# Launchpad_2021-03-10.net
KiCad netlist of a schematic drawn in EasyEDA
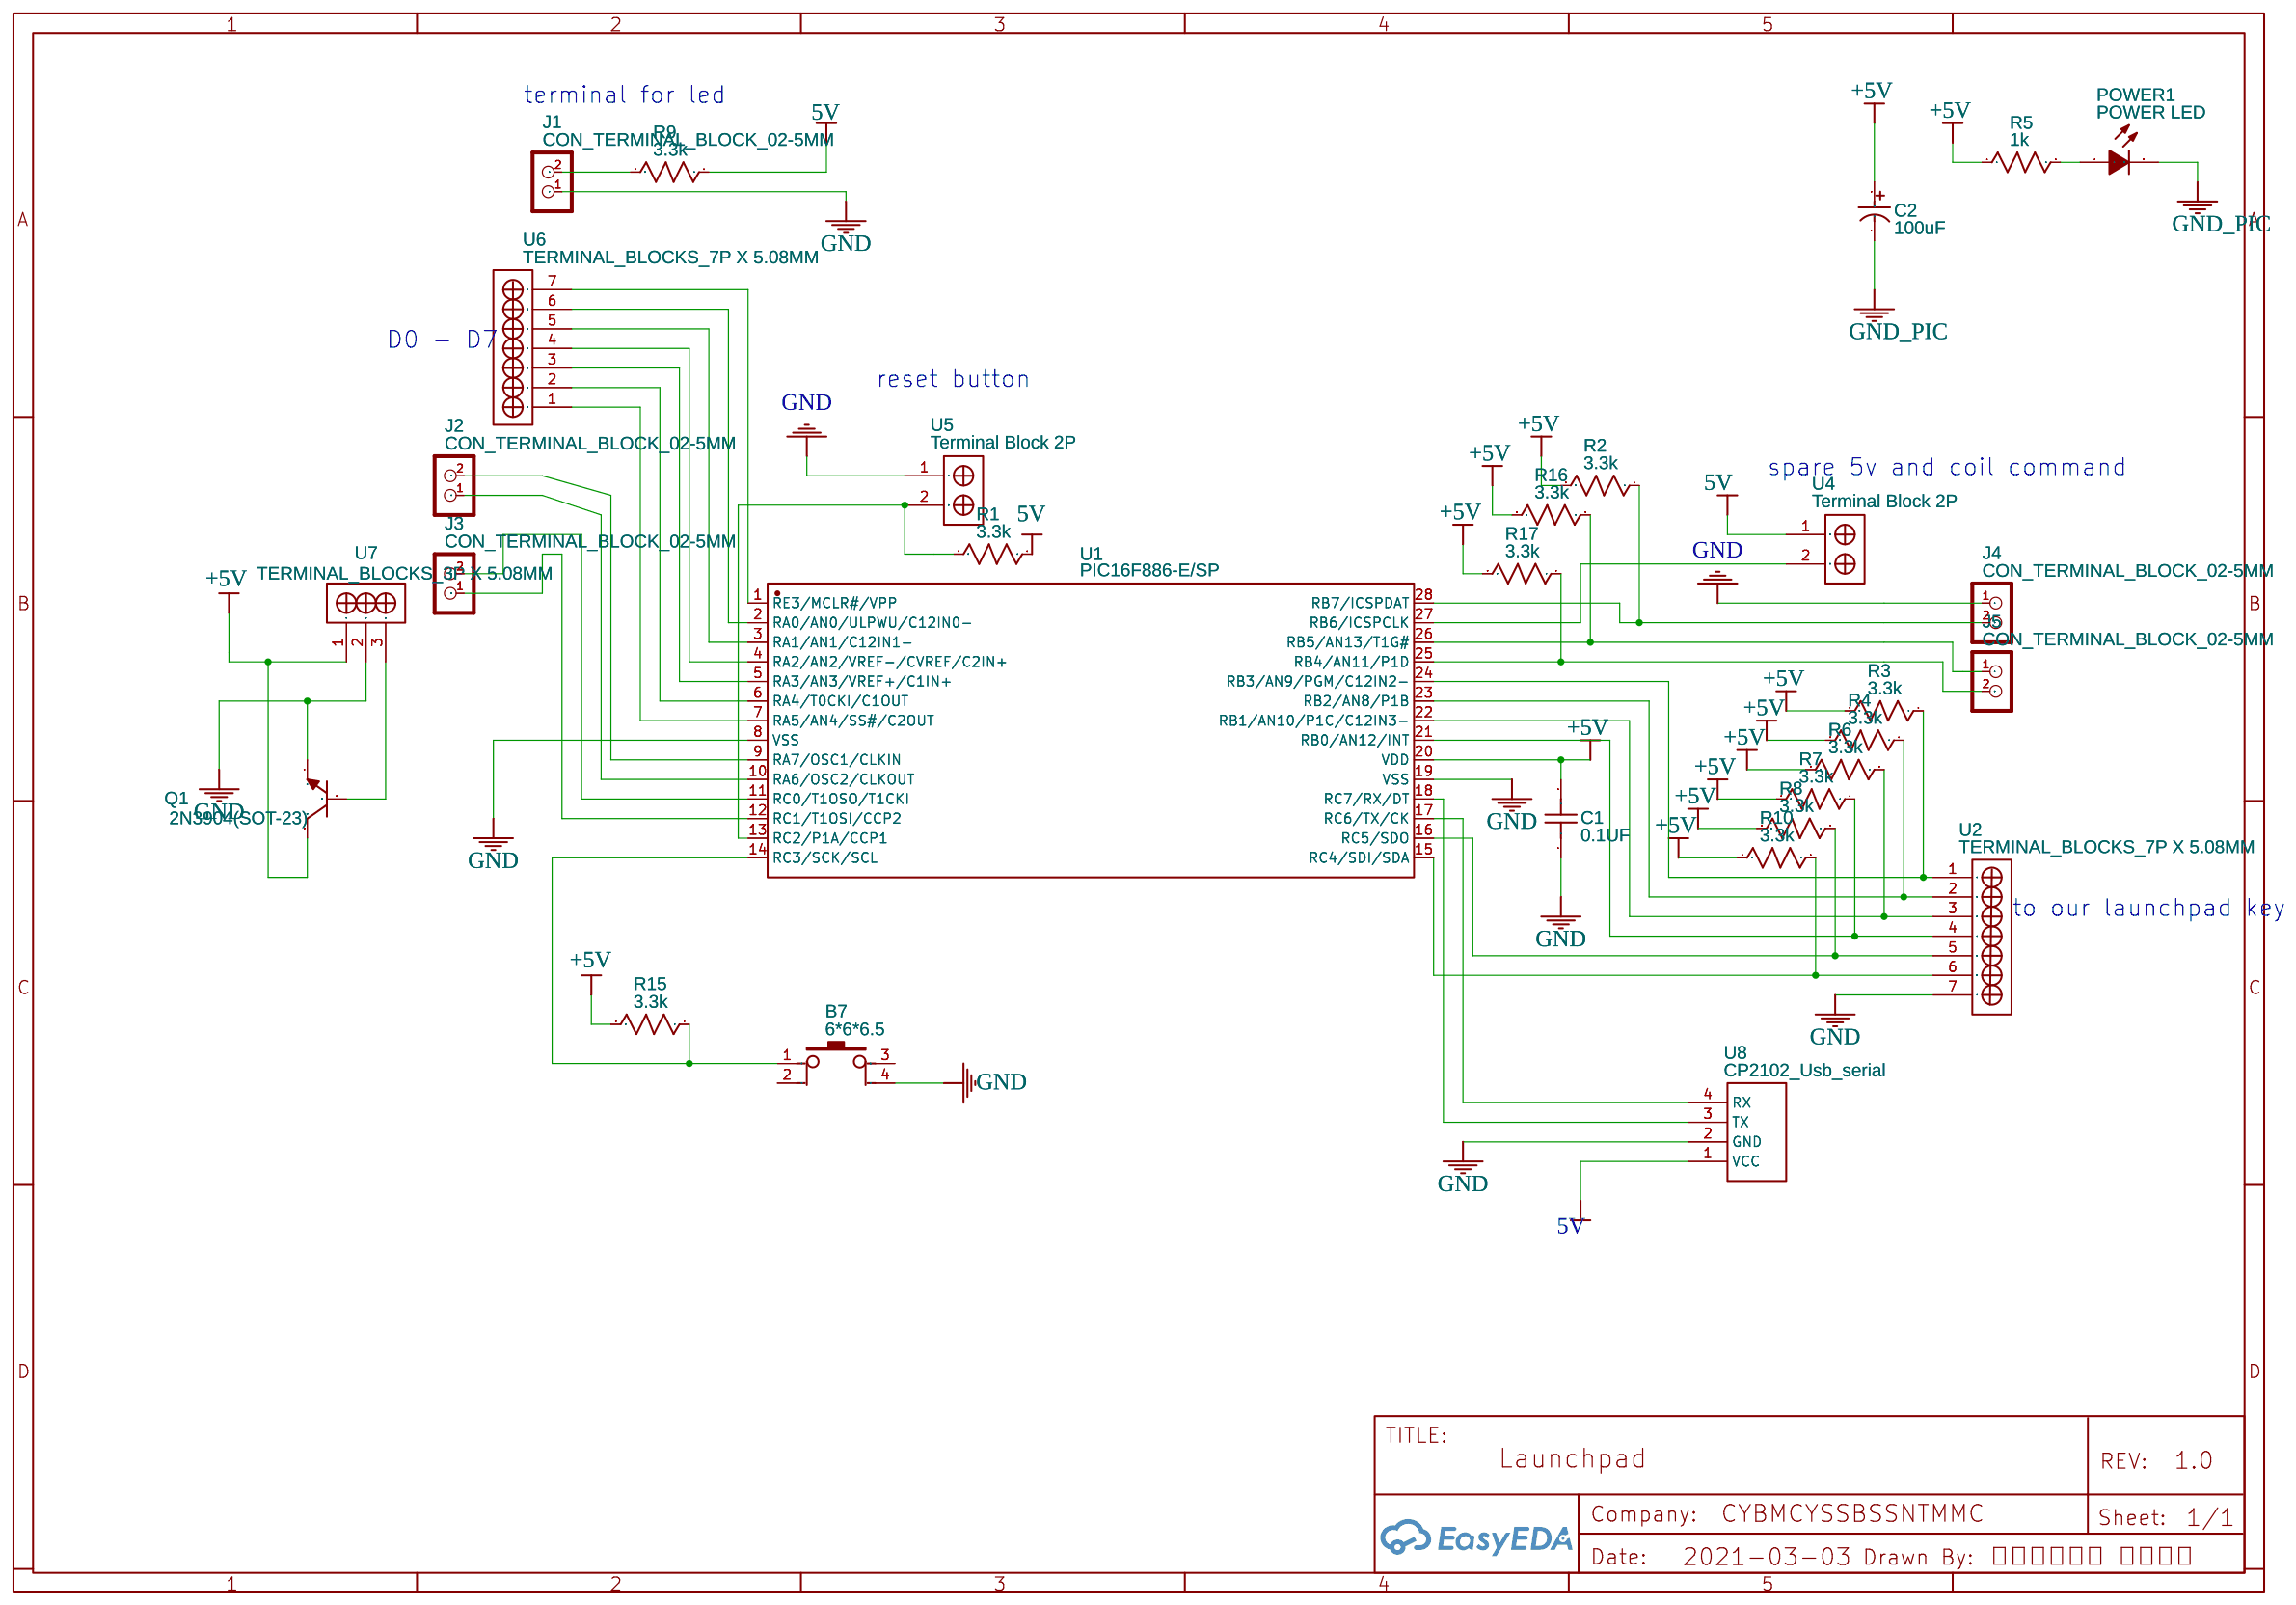
[diagram p0: schematic sheet]

(export (version "E")
  (design (tool "Eeschema 10.0.6"))
  (components
    (comp (ref "B7")
      (value "6*6*6.5")
      (fields
        (field (name "BOM_Manufacturer Part") "6*6*6.5Plastic head,260G, 0.25mm,Straight line")
        (field (name "BOM_Supplier Part") "C71841")
      )
      (libsource (lib "") (part "Unknown_420_-270"))
    )
    (comp (ref "C1")
      (value "0.1UF")
      (fields
        (field (name "BOM_Manufacturer Part") "250V 0.1UF 5% CBBCapacitor")
        (field (name "BOM_Supplier Part") "C46804")
      )
      (libsource (lib "") (part "250V 0.1UF 5% CBBCapacitor"))
    )
    (comp (ref "C2")
      (value "100uF")
      (fields (field (name "BOM_Manufacturer Part") "100uf/10V") (field (name "BOM_Supplier Part") "C2035"))
      (libsource (lib "") (part "100uf/10V"))
    )
    (comp (ref "J1")
      (value "CON_TERMINAL_BLOCK_02-5MM")
      (libsource (lib "") (part "CON_TERMINAL_BLOCK_02-5MM"))
    )
    (comp (ref "J2")
      (value "CON_TERMINAL_BLOCK_02-5MM")
      (libsource (lib "") (part "CON_TERMINAL_BLOCK_02-5MM"))
    )
    (comp (ref "J3")
      (value "CON_TERMINAL_BLOCK_02-5MM")
      (libsource (lib "") (part "CON_TERMINAL_BLOCK_02-5MM"))
    )
    (comp (ref "J4")
      (value "CON_TERMINAL_BLOCK_02-5MM")
      (libsource (lib "") (part "CON_TERMINAL_BLOCK_02-5MM_1"))
    )
    (comp (ref "J5")
      (value "CON_TERMINAL_BLOCK_02-5MM")
      (libsource (lib "") (part "CON_TERMINAL_BLOCK_02-5MM_1"))
    )
    (comp (ref "POWER1")
      (value "POWER LED")
      (fields (field (name "BOM_Manufacturer Part") "φ3 Red") (field (name "BOM_Supplier Part") "C39928"))
      (libsource (lib "") (part "Unknown_1075_-735"))
    )
    (comp (ref "Q1")
      (value "2N3904(SOT-23)")
      (fields
        (field (name "BOM_Manufacturer Part") "2n3904S-RTK/PS")
        (field (name "BOM_Supplier Part") "C18536")
      )
      (libsource (lib "") (part "2N3904(SOT-23)"))
    )
    (comp (ref "R1")
      (value "3.3k")
      (fields (field (name "BOM_Manufacturer Part") "?"))
      (libsource (lib "") (part "Res_AXIAL-0.3(1/8W)_US"))
    )
    (comp (ref "R2")
      (value "3.3k")
      (fields (field (name "BOM_Manufacturer Part") "?"))
      (libsource (lib "") (part "Res_AXIAL-0.3(1/8W)_US"))
    )
    (comp (ref "R3")
      (value "3.3k")
      (fields (field (name "BOM_Manufacturer Part") "?"))
      (libsource (lib "") (part "Res_AXIAL-0.3(1/8W)_US"))
    )
    (comp (ref "R4")
      (value "3.3k")
      (fields (field (name "BOM_Manufacturer Part") "?"))
      (libsource (lib "") (part "Res_AXIAL-0.3(1/8W)_US"))
    )
    (comp (ref "R5")
      (value "1k")
      (fields (field (name "BOM_Manufacturer Part") "?"))
      (libsource (lib "") (part "Res_AXIAL-0.3(1/8W)_US_1"))
    )
    (comp (ref "R6")
      (value "3.3k")
      (fields (field (name "BOM_Manufacturer Part") "?"))
      (libsource (lib "") (part "Res_AXIAL-0.3(1/8W)_US"))
    )
    (comp (ref "R7")
      (value "3.3k")
      (fields (field (name "BOM_Manufacturer Part") "?"))
      (libsource (lib "") (part "Res_AXIAL-0.3(1/8W)_US"))
    )
    (comp (ref "R8")
      (value "3.3k")
      (fields (field (name "BOM_Manufacturer Part") "?"))
      (libsource (lib "") (part "Res_AXIAL-0.3(1/8W)_US"))
    )
    (comp (ref "R9")
      (value "3.3k")
      (fields (field (name "BOM_Manufacturer Part") "?"))
      (libsource (lib "") (part "Res_AXIAL-0.3(1/8W)_US"))
    )
    (comp (ref "R10")
      (value "3.3k")
      (fields (field (name "BOM_Manufacturer Part") "?"))
      (libsource (lib "") (part "Res_AXIAL-0.3(1/8W)_US"))
    )
    (comp (ref "R15")
      (value "3.3k")
      (fields (field (name "BOM_Manufacturer Part") "?"))
      (libsource (lib "") (part "Res_AXIAL-0.3(1/8W)_US"))
    )
    (comp (ref "R16")
      (value "3.3k")
      (fields (field (name "BOM_Manufacturer Part") "?"))
      (libsource (lib "") (part "Res_AXIAL-0.3(1/8W)_US"))
    )
    (comp (ref "R17")
      (value "3.3k")
      (fields (field (name "BOM_Manufacturer Part") "?"))
      (libsource (lib "") (part "Res_AXIAL-0.3(1/8W)_US"))
    )
    (comp (ref "U1")
      (value "PIC16F886-E/SP")
      (fields (field (name "BOM_Supplier Part") "C647573"))
      (libsource (lib "") (part "PIC16F886-E/SP"))
    )
    (comp (ref "U2")
      (value "TERMINAL_BLOCKS_7P X 5.08MM")
      (fields
        (field (name "BOM_Manufacturer Part") "Terminal Block")
        (field (name "BOM_Supplier Part") "undefined")
      )
      (libsource (lib "") (part "TERMINAL_BLOCKS_7P X 5.08MM_1"))
    )
    (comp (ref "U4")
      (value "Terminal Block 2P")
      (fields
        (field (name "BOM_Manufacturer Part") "Terminal Block")
        (field (name "BOM_Supplier Part") "undefined")
      )
      (libsource (lib "") (part "Terminal Block 2P"))
    )
    (comp (ref "U5")
      (value "Terminal Block 2P")
      (fields
        (field (name "BOM_Manufacturer Part") "Terminal Block")
        (field (name "BOM_Supplier Part") "undefined")
      )
      (libsource (lib "") (part "Terminal Block 2P"))
    )
    (comp (ref "U6")
      (value "TERMINAL_BLOCKS_7P X 5.08MM")
      (fields
        (field (name "BOM_Manufacturer Part") "Terminal Block")
        (field (name "BOM_Supplier Part") "undefined")
      )
      (libsource (lib "") (part "TERMINAL_BLOCKS_7P X 5.08MM"))
    )
    (comp (ref "U7")
      (value "TERMINAL_BLOCKS_3P X 5.08MM")
      (fields
        (field (name "BOM_Manufacturer Part") "Terminal Block")
        (field (name "BOM_Supplier Part") "undefined")
      )
      (libsource (lib "") (part "TERMINAL_BLOCKS_3P X 5.08MM"))
    )
    (comp (ref "U8")
      (value "CP2102_Usb_serial")
      (fields (field (name "BOM_Supplier Part") "CP2102 USB UART Board (micro)"))
      (libsource (lib "") (part "CP2102_Usb_serial"))
    )
  )
  (nets
    (net (code "1") (name "+5V") (class "Default")
      (node (ref "C1") (pin "2") (pinfunction "2_2") (pintype "unspecified"))
      (node (ref "C2") (pin "1") (pinfunction "1_1") (pintype "input"))
      (node (ref "Q1") (pin "3") (pinfunction "C_3") (pintype "input"))
      (node (ref "R10") (pin "2") (pinfunction "2_2") (pintype "unspecified"))
      (node (ref "R15") (pin "2") (pinfunction "2_2") (pintype "unspecified"))
      (node (ref "R16") (pin "2") (pinfunction "2_2") (pintype "unspecified"))
      (node (ref "R17") (pin "2") (pinfunction "2_2") (pintype "unspecified"))
      (node (ref "R2") (pin "2") (pinfunction "2_2") (pintype "unspecified"))
      (node (ref "R3") (pin "2") (pinfunction "2_2") (pintype "unspecified"))
      (node (ref "R4") (pin "2") (pinfunction "2_2") (pintype "unspecified"))
      (node (ref "R5") (pin "1") (pinfunction "1_1") (pintype "unspecified"))
      (node (ref "R6") (pin "2") (pinfunction "2_2") (pintype "unspecified"))
      (node (ref "R7") (pin "2") (pinfunction "2_2") (pintype "unspecified"))
      (node (ref "R8") (pin "2") (pinfunction "2_2") (pintype "unspecified"))
      (node (ref "U1") (pin "20") (pinfunction "VDD_20") (pintype "unspecified"))
      (node (ref "U7") (pin "1") (pinfunction "1_1") (pintype "unspecified"))
    )
    (net (code "2") (name "5V") (class "Default")
      (node (ref "R1") (pin "1") (pinfunction "1_1") (pintype "unspecified"))
      (node (ref "R9") (pin "1") (pinfunction "1_1") (pintype "unspecified"))
      (node (ref "U4") (pin "1") (pinfunction "1_1") (pintype "unspecified"))
      (node (ref "U8") (pin "1") (pinfunction "VCC_1") (pintype "unspecified"))
    )
    (net (code "3") (name "GND") (class "Default")
      (node (ref "B7") (pin "4") (pinfunction "4_4") (pintype "input"))
      (node (ref "C1") (pin "1") (pinfunction "1_1") (pintype "unspecified"))
      (node (ref "J1") (pin "1") (pinfunction "1_1") (pintype "unspecified"))
      (node (ref "J4") (pin "1") (pinfunction "1_1") (pintype "unspecified"))
      (node (ref "Q1") (pin "1") (pinfunction "E_1") (pintype "input"))
      (node (ref "U1") (pin "19") (pinfunction "VSS_19") (pintype "unspecified"))
      (node (ref "U1") (pin "8") (pinfunction "VSS_8") (pintype "unspecified"))
      (node (ref "U2") (pin "7") (pinfunction "7_7") (pintype "unspecified"))
      (node (ref "U5") (pin "1") (pinfunction "1_1") (pintype "unspecified"))
      (node (ref "U7") (pin "2") (pinfunction "2_2") (pintype "unspecified"))
      (node (ref "U8") (pin "2") (pinfunction "GND_2") (pintype "unspecified"))
    )
    (net (code "4") (name "GND_PIC") (class "Default")
      (node (ref "C2") (pin "2") (pinfunction "2_2") (pintype "input"))
      (node (ref "POWER1") (pin "2") (pinfunction "C_2") (pintype "input"))
    )
    (net (code "5") (name "Net-(J1-Pad2)") (class "Default")
      (node (ref "J1") (pin "2") (pinfunction "2_2") (pintype "unspecified"))
      (node (ref "R9") (pin "2") (pinfunction "2_2") (pintype "unspecified"))
    )
    (net (code "6") (name "Net-(POWER1-A)") (class "Default")
      (node (ref "POWER1") (pin "1") (pinfunction "A_1") (pintype "input"))
      (node (ref "R5") (pin "2") (pinfunction "2_2") (pintype "unspecified"))
    )
    (net (code "7") (name "Net-(Q1-B)") (class "Default")
      (node (ref "Q1") (pin "2") (pinfunction "B_2") (pintype "input"))
      (node (ref "U7") (pin "3") (pinfunction "3_3") (pintype "unspecified"))
    )
    (net (code "8") (name "Net-(U1-RA0{slash}AN0{slash}ULPWU{slash}C12IN0-)") (class "Default")
      (node (ref "U1") (pin "2") (pinfunction "RA0/AN0/ULPWU/C12IN0-_2") (pintype "unspecified"))
      (node (ref "U6") (pin "6") (pinfunction "6_6") (pintype "unspecified"))
    )
    (net (code "9") (name "Net-(U1-RA1{slash}AN1{slash}C12IN1-)") (class "Default")
      (node (ref "U1") (pin "3") (pinfunction "RA1/AN1/C12IN1-_3") (pintype "unspecified"))
      (node (ref "U6") (pin "5") (pinfunction "5_5") (pintype "unspecified"))
    )
    (net (code "10") (name "Net-(U1-RA2{slash}AN2{slash}VREF-{slash}CVREF{slash}C2IN+)") (class "Default")
      (node (ref "U1") (pin "4") (pinfunction "RA2/AN2/VREF-/CVREF/C2IN+_4") (pintype "unspecified"))
      (node (ref "U6") (pin "4") (pinfunction "4_4") (pintype "unspecified"))
    )
    (net (code "11") (name "Net-(U1-RA3{slash}AN3{slash}VREF+{slash}C1IN+)") (class "Default")
      (node (ref "U1") (pin "5") (pinfunction "RA3/AN3/VREF+/C1IN+_5") (pintype "unspecified"))
      (node (ref "U6") (pin "3") (pinfunction "3_3") (pintype "unspecified"))
    )
    (net (code "12") (name "Net-(U1-RA4{slash}T0CKI{slash}C1OUT)") (class "Default")
      (node (ref "U1") (pin "6") (pinfunction "RA4/T0CKI/C1OUT_6") (pintype "unspecified"))
      (node (ref "U6") (pin "2") (pinfunction "2_2") (pintype "unspecified"))
    )
    (net (code "13") (name "Net-(U1-RA5{slash}AN4{slash}SS#{slash}C2OUT)") (class "Default")
      (node (ref "U1") (pin "7") (pinfunction "RA5/AN4/SS#/C2OUT_7") (pintype "unspecified"))
      (node (ref "U6") (pin "1") (pinfunction "1_1") (pintype "unspecified"))
    )
    (net (code "14") (name "Net-(U1-RA6{slash}OSC2{slash}CLKOUT)") (class "Default")
      (node (ref "J2") (pin "1") (pinfunction "1_1") (pintype "unspecified"))
      (node (ref "U1") (pin "10") (pinfunction "RA6/OSC2/CLKOUT_10") (pintype "unspecified"))
    )
    (net (code "15") (name "Net-(U1-RA7{slash}OSC1{slash}CLKIN)") (class "Default")
      (node (ref "J2") (pin "2") (pinfunction "2_2") (pintype "unspecified"))
      (node (ref "U1") (pin "9") (pinfunction "RA7/OSC1/CLKIN_9") (pintype "unspecified"))
    )
    (net (code "16") (name "Net-(U1-RB0{slash}AN12{slash}INT)") (class "Default")
      (node (ref "R7") (pin "1") (pinfunction "1_1") (pintype "unspecified"))
      (node (ref "U1") (pin "21") (pinfunction "RB0/AN12/INT_21") (pintype "unspecified"))
      (node (ref "U2") (pin "4") (pinfunction "4_4") (pintype "unspecified"))
    )
    (net (code "17") (name "Net-(U1-RB1{slash}AN10{slash}P1C{slash}C12IN3-)") (class "Default")
      (node (ref "R6") (pin "1") (pinfunction "1_1") (pintype "unspecified"))
      (node (ref "U1") (pin "22") (pinfunction "RB1/AN10/P1C/C12IN3-_22") (pintype "unspecified"))
      (node (ref "U2") (pin "3") (pinfunction "3_3") (pintype "unspecified"))
    )
    (net (code "18") (name "Net-(U1-RB2{slash}AN8{slash}P1B)") (class "Default")
      (node (ref "R4") (pin "1") (pinfunction "1_1") (pintype "unspecified"))
      (node (ref "U1") (pin "23") (pinfunction "RB2/AN8/P1B_23") (pintype "unspecified"))
      (node (ref "U2") (pin "2") (pinfunction "2_2") (pintype "unspecified"))
    )
    (net (code "19") (name "Net-(U1-RB3{slash}AN9{slash}PGM{slash}C12IN2-)") (class "Default")
      (node (ref "R3") (pin "1") (pinfunction "1_1") (pintype "unspecified"))
      (node (ref "U1") (pin "24") (pinfunction "RB3/AN9/PGM/C12IN2-_24") (pintype "unspecified"))
      (node (ref "U2") (pin "1") (pinfunction "1_1") (pintype "unspecified"))
    )
    (net (code "20") (name "Net-(U1-RB4{slash}AN11{slash}P1D)") (class "Default")
      (node (ref "J5") (pin "2") (pinfunction "2_2") (pintype "unspecified"))
      (node (ref "R17") (pin "1") (pinfunction "1_1") (pintype "unspecified"))
      (node (ref "U1") (pin "25") (pinfunction "RB4/AN11/P1D_25") (pintype "unspecified"))
    )
    (net (code "21") (name "Net-(U1-RB5{slash}AN13{slash}T1G#)") (class "Default")
      (node (ref "J5") (pin "1") (pinfunction "1_1") (pintype "unspecified"))
      (node (ref "R16") (pin "1") (pinfunction "1_1") (pintype "unspecified"))
      (node (ref "U1") (pin "26") (pinfunction "RB5/AN13/T1G#_26") (pintype "unspecified"))
    )
    (net (code "22") (name "Net-(U1-RB6{slash}ICSPCLK)") (class "Default")
      (node (ref "U1") (pin "27") (pinfunction "RB6/ICSPCLK_27") (pintype "unspecified"))
      (node (ref "U4") (pin "2") (pinfunction "2_2") (pintype "unspecified"))
    )
    (net (code "23") (name "Net-(U1-RB7{slash}ICSPDAT)") (class "Default")
      (node (ref "J4") (pin "2") (pinfunction "2_2") (pintype "unspecified"))
      (node (ref "R2") (pin "1") (pinfunction "1_1") (pintype "unspecified"))
      (node (ref "U1") (pin "28") (pinfunction "RB7/ICSPDAT_28") (pintype "unspecified"))
    )
    (net (code "24") (name "Net-(U1-RC0{slash}T1OSO{slash}T1CKI)") (class "Default")
      (node (ref "J3") (pin "2") (pinfunction "2_2") (pintype "unspecified"))
      (node (ref "U1") (pin "11") (pinfunction "RC0/T1OSO/T1CKI_11") (pintype "unspecified"))
    )
    (net (code "25") (name "Net-(U1-RC1{slash}T1OSI{slash}CCP2)") (class "Default")
      (node (ref "J3") (pin "1") (pinfunction "1_1") (pintype "unspecified"))
      (node (ref "U1") (pin "12") (pinfunction "RC1/T1OSI/CCP2_12") (pintype "unspecified"))
    )
    (net (code "26") (name "Net-(U1-RC2{slash}P1A{slash}CCP1)") (class "Default")
      (node (ref "R1") (pin "2") (pinfunction "2_2") (pintype "unspecified"))
      (node (ref "U1") (pin "13") (pinfunction "RC2/P1A/CCP1_13") (pintype "unspecified"))
      (node (ref "U5") (pin "2") (pinfunction "2_2") (pintype "unspecified"))
    )
    (net (code "27") (name "Net-(U1-RC3{slash}SCK{slash}SCL)") (class "Default")
      (node (ref "B7") (pin "1") (pinfunction "1_1") (pintype "input"))
      (node (ref "R15") (pin "1") (pinfunction "1_1") (pintype "unspecified"))
      (node (ref "U1") (pin "14") (pinfunction "RC3/SCK/SCL_14") (pintype "unspecified"))
    )
    (net (code "28") (name "Net-(U1-RC4{slash}SDI{slash}SDA)") (class "Default")
      (node (ref "R10") (pin "1") (pinfunction "1_1") (pintype "unspecified"))
      (node (ref "U1") (pin "15") (pinfunction "RC4/SDI/SDA_15") (pintype "unspecified"))
      (node (ref "U2") (pin "6") (pinfunction "6_6") (pintype "unspecified"))
    )
    (net (code "29") (name "Net-(U1-RC5{slash}SDO)") (class "Default")
      (node (ref "R8") (pin "1") (pinfunction "1_1") (pintype "unspecified"))
      (node (ref "U1") (pin "16") (pinfunction "RC5/SDO_16") (pintype "unspecified"))
      (node (ref "U2") (pin "5") (pinfunction "5_5") (pintype "unspecified"))
    )
    (net (code "30") (name "Net-(U1-RC6{slash}TX{slash}CK)") (class "Default")
      (node (ref "U1") (pin "17") (pinfunction "RC6/TX/CK_17") (pintype "unspecified"))
      (node (ref "U8") (pin "4") (pinfunction "RX_4") (pintype "unspecified"))
    )
    (net (code "31") (name "Net-(U1-RC7{slash}RX{slash}DT)") (class "Default")
      (node (ref "U1") (pin "18") (pinfunction "RC7/RX/DT_18") (pintype "unspecified"))
      (node (ref "U8") (pin "3") (pinfunction "TX_3") (pintype "unspecified"))
    )
    (net (code "32") (name "Net-(U1-RE3{slash}MCLR#{slash}VPP)") (class "Default")
      (node (ref "U1") (pin "1") (pinfunction "RE3/MCLR#/VPP_1") (pintype "unspecified"))
      (node (ref "U6") (pin "7") (pinfunction "7_7") (pintype "unspecified"))
    )
    (net (code "33") (name "unconnected-(B7-Pad2)") (class "Default")
      (node (ref "B7") (pin "2") (pinfunction "2_2") (pintype "input"))
    )
    (net (code "34") (name "unconnected-(B7-Pad3)") (class "Default")
      (node (ref "B7") (pin "3") (pinfunction "3_3") (pintype "input"))
    )
  )
)
